# Hip_SMD_V1.net
KiCad netlist of a schematic drawn in EAGLE
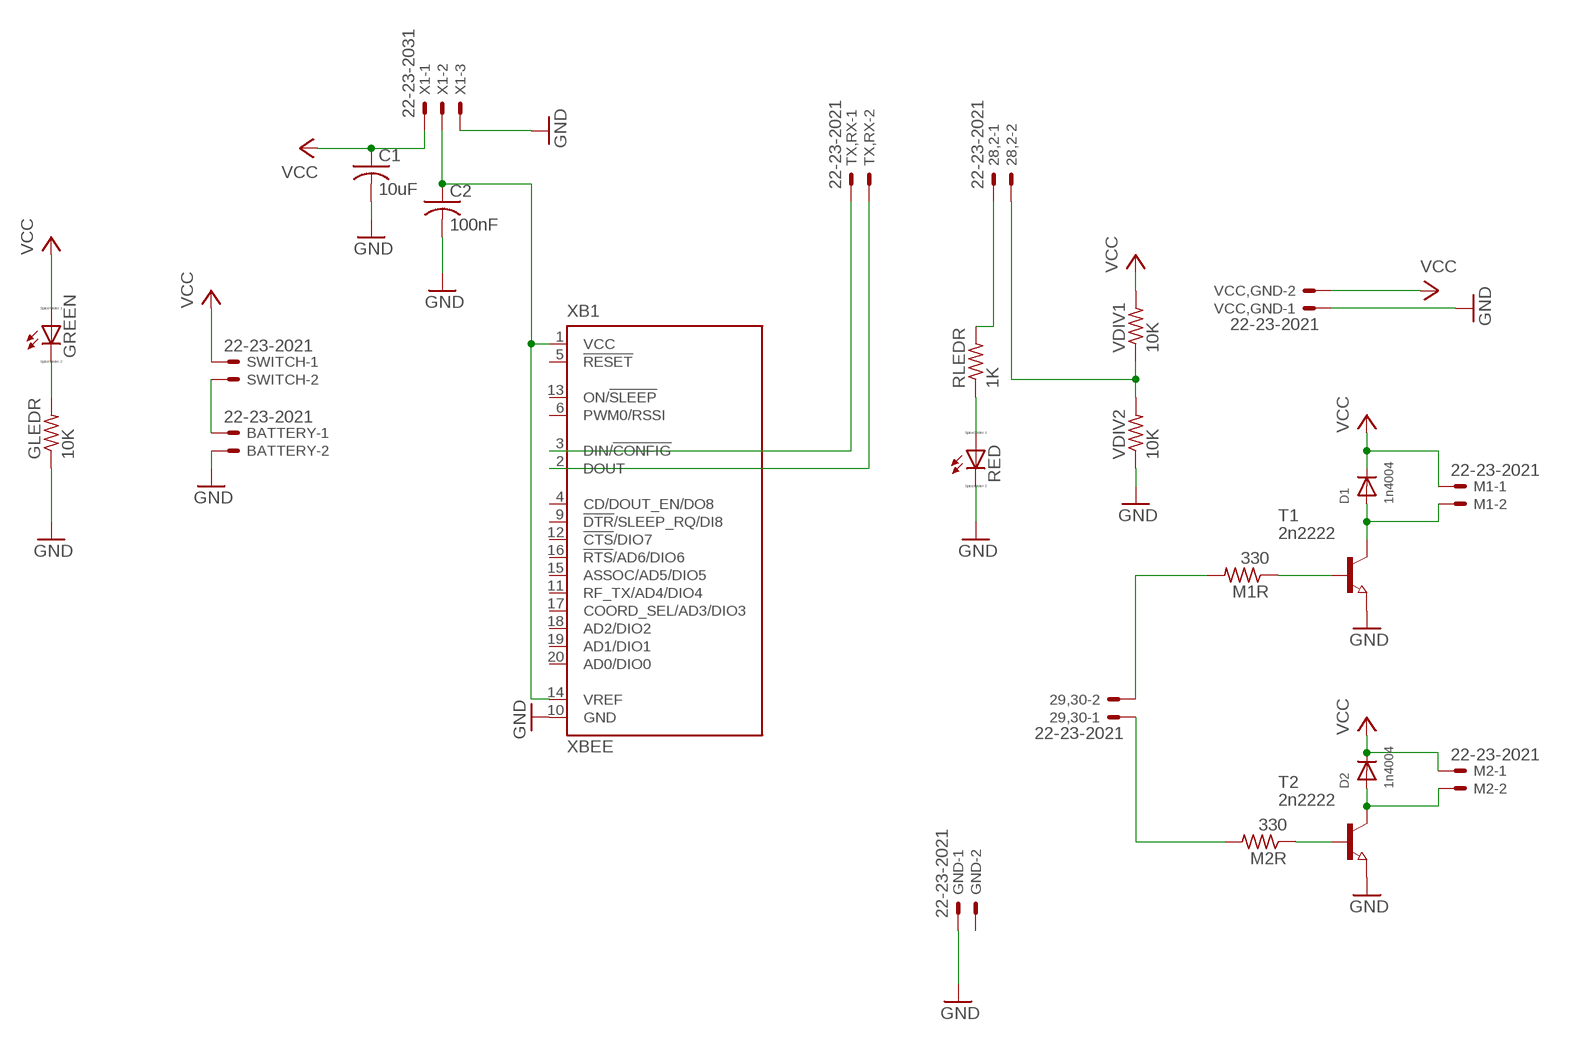
[diagram p0: schematic, sheet 1]

(export (version "E")
  (design (tool "Eeschema 10.0.6"))
  (components
    (comp (ref "28,2")
      (value "22-23-2021")
      (footprint "eagle-import:22-23-2021")
      (fields (field (name "MF") "MOLEX"))
      (libsource (lib "eagle-import") (part "22-23-2021"))
    )
    (comp (ref "29,30")
      (value "22-23-2021")
      (footprint "eagle-import:22-23-2021")
      (fields (field (name "MF") "MOLEX"))
      (libsource (lib "eagle-import") (part "22-23-2021"))
    )
    (comp (ref "BATTERY")
      (value "22-23-2021")
      (footprint "eagle-import:22-23-2021")
      (fields (field (name "MF") "MOLEX"))
      (libsource (lib "eagle-import") (part "22-23-2021"))
    )
    (comp (ref "C1")
      (value "10uF")
      (footprint "eagle-import:C1206")
      (libsource (lib "eagle-import") (part "C-USC1206"))
    )
    (comp (ref "C2")
      (value "100nF")
      (footprint "eagle-import:C1206")
      (libsource (lib "eagle-import") (part "C-USC1206"))
    )
    (comp (ref "D1")
      (value "1n4004")
      (footprint "eagle-import:SMADIODE")
      (libsource (lib "eagle-import") (part "DIODESMA"))
    )
    (comp (ref "D2")
      (value "1n4004")
      (footprint "eagle-import:SMADIODE")
      (libsource (lib "eagle-import") (part "DIODESMA"))
    )
    (comp (ref "GLEDR")
      (value "10K")
      (footprint "eagle-import:M1206")
      (libsource (lib "eagle-import") (part "R-US_M1206"))
    )
    (comp (ref "GND")
      (value "22-23-2021")
      (footprint "eagle-import:22-23-2021")
      (fields (field (name "MF") "MOLEX"))
      (libsource (lib "eagle-import") (part "22-23-2021"))
    )
    (comp (ref "GREEN")
      (value "LED_E")
      (footprint "eagle-import:LED_1206")
      (libsource (lib "eagle-import") (part "LED_E"))
    )
    (comp (ref "M1")
      (value "22-23-2021")
      (footprint "eagle-import:22-23-2021")
      (fields (field (name "MF") "MOLEX"))
      (libsource (lib "eagle-import") (part "22-23-2021"))
    )
    (comp (ref "M1R")
      (value "330")
      (footprint "eagle-import:M1206")
      (libsource (lib "eagle-import") (part "R-US_M1206"))
    )
    (comp (ref "M2")
      (value "22-23-2021")
      (footprint "eagle-import:22-23-2021")
      (fields (field (name "MF") "MOLEX"))
      (libsource (lib "eagle-import") (part "22-23-2021"))
    )
    (comp (ref "M2R")
      (value "330")
      (footprint "eagle-import:M1206")
      (libsource (lib "eagle-import") (part "R-US_M1206"))
    )
    (comp (ref "RED")
      (value "LED_E")
      (footprint "eagle-import:LED_1206")
      (libsource (lib "eagle-import") (part "LED_E"))
    )
    (comp (ref "RLEDR")
      (value "1K")
      (footprint "eagle-import:M1206")
      (libsource (lib "eagle-import") (part "R-US_M1206"))
    )
    (comp (ref "SWITCH")
      (value "22-23-2021")
      (footprint "eagle-import:22-23-2021")
      (fields (field (name "MF") "MOLEX"))
      (libsource (lib "eagle-import") (part "22-23-2021"))
    )
    (comp (ref "T1")
      (value "2n2222")
      (footprint "eagle-import:SOT23")
      (libsource (lib "eagle-import") (part "NPN-TRANSISTOR_SOT23"))
    )
    (comp (ref "T2")
      (value "2n2222")
      (footprint "eagle-import:SOT23")
      (libsource (lib "eagle-import") (part "NPN-TRANSISTOR_SOT23"))
    )
    (comp (ref "TX,RX")
      (value "22-23-2021")
      (footprint "eagle-import:22-23-2021")
      (fields (field (name "MF") "MOLEX"))
      (libsource (lib "eagle-import") (part "22-23-2021"))
    )
    (comp (ref "VCC,GND")
      (value "22-23-2021")
      (footprint "eagle-import:22-23-2021")
      (fields (field (name "MF") "MOLEX"))
      (libsource (lib "eagle-import") (part "22-23-2021"))
    )
    (comp (ref "VDIV1")
      (value "10K")
      (footprint "eagle-import:M1206")
      (libsource (lib "eagle-import") (part "R-US_M1206"))
    )
    (comp (ref "VDIV2")
      (value "10K")
      (footprint "eagle-import:M1206")
      (libsource (lib "eagle-import") (part "R-US_M1206"))
    )
    (comp (ref "X1")
      (value "22-23-2031")
      (footprint "eagle-import:22-23-2031")
      (fields (field (name "MF") "MOLEX"))
      (libsource (lib "eagle-import") (part "22-23-2031"))
    )
    (comp (ref "XB1")
      (value "XBEE")
      (footprint "eagle-import:XBEE")
      (fields (field (name "MPN") "XBP24-Z7UIT-004"))
      (libsource (lib "eagle-import") (part "XBEE"))
    )
  )
  (nets
    (net (code "1") (name "GND") (class "Default")
      (node (ref "BATTERY") (pin "2") (pinfunction "S_2") (pintype "passive"))
      (node (ref "C1") (pin "2") (pinfunction "2_2") (pintype "passive"))
      (node (ref "C2") (pin "2") (pinfunction "2_2") (pintype "passive"))
      (node (ref "GLEDR") (pin "1") (pinfunction "1_1") (pintype "passive"))
      (node (ref "GND") (pin "1") (pinfunction "S_1") (pintype "passive"))
      (node (ref "RED") (pin "C") (pinfunction "C_C") (pintype "passive"))
      (node (ref "T1") (pin "2") (pinfunction "E_2") (pintype "passive"))
      (node (ref "T2") (pin "2") (pinfunction "E_2") (pintype "passive"))
      (node (ref "VCC,GND") (pin "1") (pinfunction "S_1") (pintype "passive"))
      (node (ref "VDIV2") (pin "1") (pinfunction "1_1") (pintype "passive"))
      (node (ref "X1") (pin "3") (pinfunction "S_3") (pintype "passive"))
      (node (ref "XB1") (pin "10") (pinfunction "GND_10") (pintype "power_in"))
    )
    (net (code "2") (name "Net-(28,2A-S)") (class "Default")
      (node (ref "28,2") (pin "1") (pinfunction "S_1") (pintype "passive"))
      (node (ref "RLEDR") (pin "2") (pinfunction "2_2") (pintype "passive"))
    )
    (net (code "3") (name "Net-(28,2B-S)") (class "Default")
      (node (ref "28,2") (pin "2") (pinfunction "S_2") (pintype "passive"))
      (node (ref "VDIV1") (pin "1") (pinfunction "1_1") (pintype "passive"))
      (node (ref "VDIV2") (pin "2") (pinfunction "2_2") (pintype "passive"))
    )
    (net (code "4") (name "Net-(29,30A-S)") (class "Default")
      (node (ref "29,30") (pin "1") (pinfunction "S_1") (pintype "passive"))
      (node (ref "M2R") (pin "2") (pinfunction "2_2") (pintype "passive"))
    )
    (net (code "5") (name "Net-(29,30B-S)") (class "Default")
      (node (ref "29,30") (pin "2") (pinfunction "S_2") (pintype "passive"))
      (node (ref "M1R") (pin "2") (pinfunction "2_2") (pintype "passive"))
    )
    (net (code "6") (name "Net-(BATTERYA-S)") (class "Default")
      (node (ref "BATTERY") (pin "1") (pinfunction "S_1") (pintype "passive"))
      (node (ref "SWITCH") (pin "2") (pinfunction "S_2") (pintype "passive"))
    )
    (net (code "7") (name "Net-(GLEDR-Pad2)") (class "Default")
      (node (ref "GLEDR") (pin "2") (pinfunction "2_2") (pintype "passive"))
      (node (ref "GREEN") (pin "C") (pinfunction "C_C") (pintype "passive"))
    )
    (net (code "8") (name "Net-(M1B-S)") (class "Default")
      (node (ref "D1") (pin "A") (pinfunction "A_A") (pintype "passive"))
      (node (ref "M1") (pin "2") (pinfunction "S_2") (pintype "passive"))
      (node (ref "T1") (pin "3") (pinfunction "C_3") (pintype "passive"))
    )
    (net (code "9") (name "Net-(M2B-S)") (class "Default")
      (node (ref "D2") (pin "A") (pinfunction "A_A") (pintype "passive"))
      (node (ref "M2") (pin "2") (pinfunction "S_2") (pintype "passive"))
      (node (ref "T2") (pin "3") (pinfunction "C_3") (pintype "passive"))
    )
    (net (code "10") (name "Net-(RED-PadA)") (class "Default")
      (node (ref "RED") (pin "A") (pinfunction "A_A") (pintype "passive"))
      (node (ref "RLEDR") (pin "1") (pinfunction "1_1") (pintype "passive"))
    )
    (net (code "11") (name "Net-(T1-B)") (class "Default")
      (node (ref "M1R") (pin "1") (pinfunction "1_1") (pintype "passive"))
      (node (ref "T1") (pin "1") (pinfunction "B_1") (pintype "passive"))
    )
    (net (code "12") (name "Net-(T2-B)") (class "Default")
      (node (ref "M2R") (pin "1") (pinfunction "1_1") (pintype "passive"))
      (node (ref "T2") (pin "1") (pinfunction "B_1") (pintype "passive"))
    )
    (net (code "13") (name "Net-(TX,RXA-S)") (class "Default")
      (node (ref "TX,RX") (pin "1") (pinfunction "S_1") (pintype "passive"))
      (node (ref "XB1") (pin "3") (pinfunction "DIN/~{CONFIG}_3") (pintype "input"))
    )
    (net (code "14") (name "Net-(TX,RXB-S)") (class "Default")
      (node (ref "TX,RX") (pin "2") (pinfunction "S_2") (pintype "passive"))
      (node (ref "XB1") (pin "2") (pinfunction "DOUT_2") (pintype "output"))
    )
    (net (code "15") (name "Net-(X1B-S)") (class "Default")
      (node (ref "C2") (pin "1") (pinfunction "1_1") (pintype "passive"))
      (node (ref "X1") (pin "2") (pinfunction "S_2") (pintype "passive"))
      (node (ref "XB1") (pin "1") (pinfunction "VCC_1") (pintype "power_in"))
      (node (ref "XB1") (pin "14") (pinfunction "VREF_14") (pintype "input"))
    )
    (net (code "16") (name "VCC") (class "Default")
      (node (ref "C1") (pin "1") (pinfunction "1_1") (pintype "passive"))
      (node (ref "D1") (pin "C") (pinfunction "C_C") (pintype "passive"))
      (node (ref "D2") (pin "C") (pinfunction "C_C") (pintype "passive"))
      (node (ref "GREEN") (pin "A") (pinfunction "A_A") (pintype "passive"))
      (node (ref "M1") (pin "1") (pinfunction "S_1") (pintype "passive"))
      (node (ref "M2") (pin "1") (pinfunction "S_1") (pintype "passive"))
      (node (ref "SWITCH") (pin "1") (pinfunction "S_1") (pintype "passive"))
      (node (ref "VCC,GND") (pin "2") (pinfunction "S_2") (pintype "passive"))
      (node (ref "VDIV1") (pin "2") (pinfunction "2_2") (pintype "passive"))
      (node (ref "X1") (pin "1") (pinfunction "S_1") (pintype "passive"))
    )
    (net (code "17") (name "unconnected-(GNDB-S-Pad2)") (class "Default")
      (node (ref "GND") (pin "2") (pinfunction "S_2") (pintype "passive"))
    )
    (net (code "18") (name "unconnected-(XB1-AD0{slash}DIO0-Pad20)") (class "Default")
      (node (ref "XB1") (pin "20") (pinfunction "AD0/DIO0_20") (pintype "bidirectional"))
    )
    (net (code "19") (name "unconnected-(XB1-AD1{slash}DIO1-Pad19)") (class "Default")
      (node (ref "XB1") (pin "19") (pinfunction "AD1/DIO1_19") (pintype "bidirectional"))
    )
    (net (code "20") (name "unconnected-(XB1-AD2{slash}DIO2-Pad18)") (class "Default")
      (node (ref "XB1") (pin "18") (pinfunction "AD2/DIO2_18") (pintype "bidirectional"))
    )
    (net (code "21") (name "unconnected-(XB1-ASSOC{slash}AD5{slash}DIO5-Pad15)") (class "Default")
      (node (ref "XB1") (pin "15") (pinfunction "ASSOC/AD5/DIO5_15") (pintype "bidirectional"))
    )
    (net (code "22") (name "unconnected-(XB1-CD{slash}DOUT_EN{slash}DO8-Pad4)") (class "Default")
      (node (ref "XB1") (pin "4") (pinfunction "CD/DOUT_EN/DO8_4") (pintype "output"))
    )
    (net (code "23") (name "unconnected-(XB1-COORD_SEL{slash}AD3{slash}DIO3-Pad17)") (class "Default")
      (node (ref "XB1") (pin "17") (pinfunction "COORD_SEL/AD3/DIO3_17") (pintype "bidirectional"))
    )
    (net (code "24") (name "unconnected-(XB1-ON{slash}~{SLEEP}-Pad13)") (class "Default")
      (node (ref "XB1") (pin "13") (pinfunction "ON/~{SLEEP}_13") (pintype "output"))
    )
    (net (code "25") (name "unconnected-(XB1-PWM0{slash}RSSI-Pad6)") (class "Default")
      (node (ref "XB1") (pin "6") (pinfunction "PWM0/RSSI_6") (pintype "output"))
    )
    (net (code "26") (name "unconnected-(XB1-RF_TX{slash}AD4{slash}DIO4-Pad11)") (class "Default")
      (node (ref "XB1") (pin "11") (pinfunction "RF_TX/AD4/DIO4_11") (pintype "bidirectional"))
    )
    (net (code "27") (name "unconnected-(XB1-~{CTS}{slash}DIO7-Pad12)") (class "Default")
      (node (ref "XB1") (pin "12") (pinfunction "~{CTS}/DIO7_12") (pintype "bidirectional"))
    )
    (net (code "28") (name "unconnected-(XB1-~{DTR}{slash}SLEEP_RQ{slash}DI8-Pad9)") (class "Default")
      (node (ref "XB1") (pin "9") (pinfunction "~{DTR}/SLEEP_RQ/DI8_9") (pintype "bidirectional"))
    )
    (net (code "29") (name "unconnected-(XB1-~{RESET}-Pad5)") (class "Default")
      (node (ref "XB1") (pin "5") (pinfunction "~{RESET}_5") (pintype "input"))
    )
    (net (code "30") (name "unconnected-(XB1-~{RTS}{slash}AD6{slash}DIO6-Pad16)") (class "Default")
      (node (ref "XB1") (pin "16") (pinfunction "~{RTS}/AD6/DIO6_16") (pintype "bidirectional"))
    )
  )
)
